# mapleCUx_large_400-003.net
KiCad netlist of a schematic drawn in EAGLE
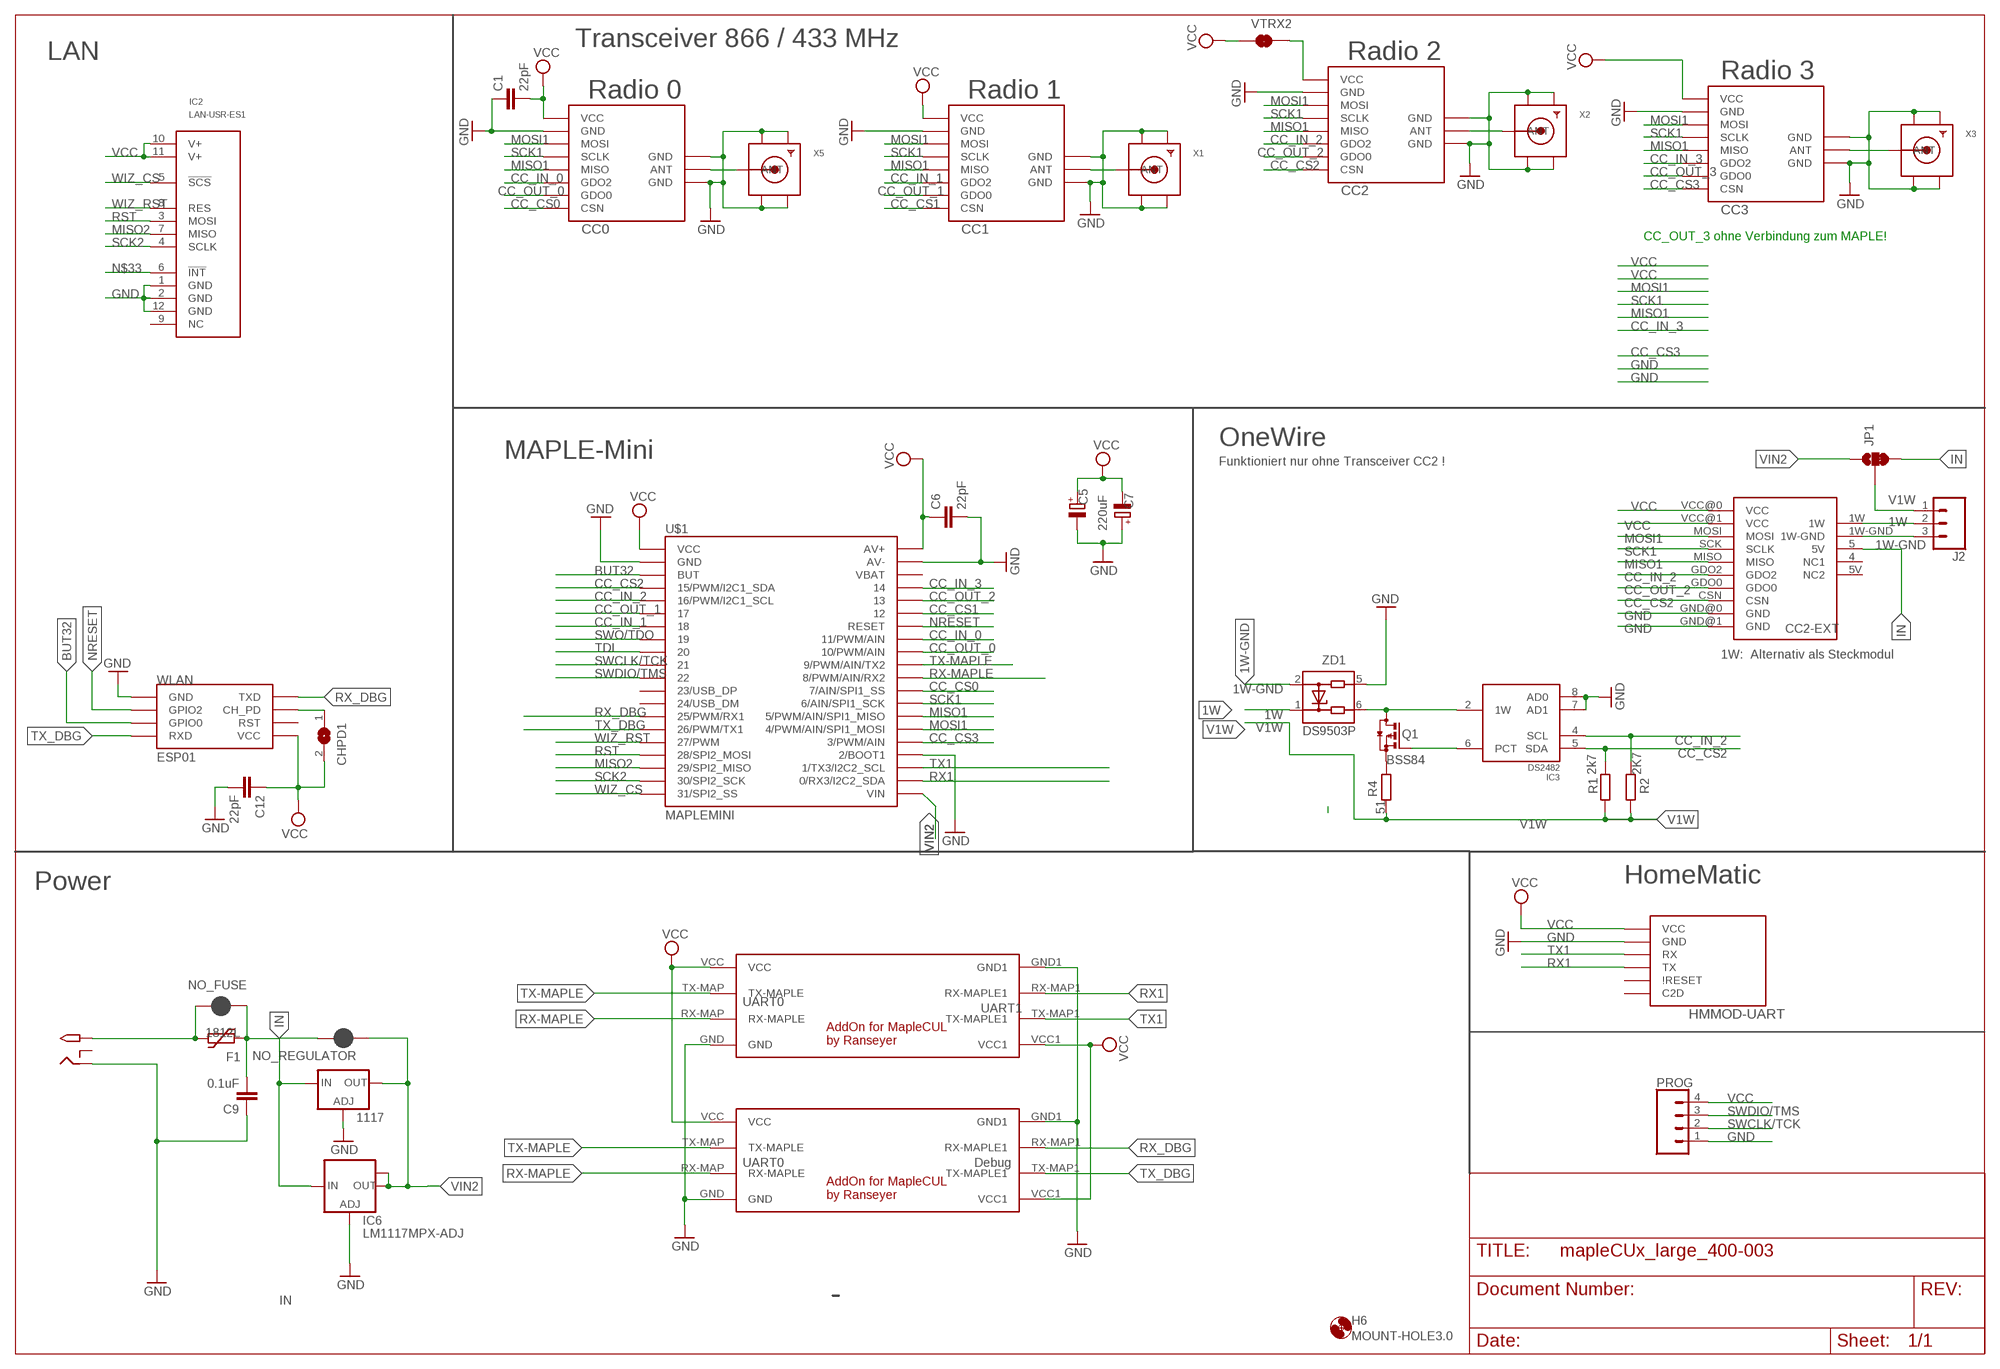
[diagram p0: schematic, sheet 1]

(export (version "E")
  (design (tool "Eeschema 10.0.6"))
  (components
    (comp (ref "1117")
      (value "LD117ADT50TR")
      (footprint "eagle-import:DPACK")
      (libsource (lib "eagle-import") (part "LD117A?DT50TR"))
    )
    (comp (ref "C1")
      (value "22pF")
      (footprint "eagle-import:C0805")
      (libsource (lib "eagle-import") (part "C-EUC0805"))
    )
    (comp (ref "C5")
      (value "220uF")
      (footprint "eagle-import:E5-8,5")
      (libsource (lib "eagle-import") (part "CPOL-EUE5-8.5"))
    )
    (comp (ref "C6")
      (value "22pF")
      (footprint "eagle-import:C0805")
      (libsource (lib "eagle-import") (part "C-EUC0805"))
    )
    (comp (ref "C7")
      (value "CPOL-EUSMCE")
      (footprint "eagle-import:SMC_E")
      (libsource (lib "eagle-import") (part "rcl_334_CPOL-EUSMCE"))
    )
    (comp (ref "C9")
      (value "0.1uF")
      (footprint "eagle-import:C1206")
      (libsource (lib "eagle-import") (part "C-EUC1206"))
    )
    (comp (ref "C12")
      (value "22pF")
      (footprint "eagle-import:C0805")
      (libsource (lib "eagle-import") (part "C-EUC0805"))
    )
    (comp (ref "CC0")
      (value "CC1101")
      (footprint "eagle-import:CC1101_MODULE1_SMD")
      (libsource (lib "eagle-import") (part "CC1101_MODULE1SMD"))
    )
    (comp (ref "CC1")
      (value "CC1101_MODULE1SMD")
      (footprint "eagle-import:CC1101_MODULE1_SMD")
      (libsource (lib "eagle-import") (part "CC1101_MODULE1SMD"))
    )
    (comp (ref "CC2")
      (value "CC1101_MODULE1SMD")
      (footprint "eagle-import:CC1101_MODULE1_SMD")
      (libsource (lib "eagle-import") (part "CC1101_MODULE1SMD"))
    )
    (comp (ref "CC2-EXT")
      (value "ONEWIRE-MODULE")
      (footprint "eagle-import:ONEWIRE_CC1101_MODULE3_DIL")
      (libsource (lib "eagle-import") (part "ONEWIRE-MODULE"))
    )
    (comp (ref "CC3")
      (value "CC1101_MODULE1SMD")
      (footprint "eagle-import:CC1101_MODULE1_SMD")
      (libsource (lib "eagle-import") (part "CC1101_MODULE1SMD"))
    )
    (comp (ref "CHPD1")
      (value "SJ")
      (footprint "eagle-import:SJ")
      (libsource (lib "eagle-import") (part "SJ"))
    )
    (comp (ref "F1")
      (value "1812L")
      (footprint "eagle-import:1812L")
      (libsource (lib "eagle-import") (part "1812L"))
    )
    (comp (ref "H6")
      (value "MOUNT-HOLE3.0")
      (footprint "eagle-import:3,0")
      (libsource (lib "eagle-import") (part "MOUNT-HOLE3.0"))
    )
    (comp (ref "HMMOD-UART")
      (value "HM-MOD-UARTDIL")
      (footprint "eagle-import:HM-MOD-UART-DIL")
      (libsource (lib "eagle-import") (part "HM-MOD-UARTDIL"))
    )
    (comp (ref "IC2")
      (value "LAN-USR-ES1")
      (footprint "eagle-import:USR-ES1")
      (libsource (lib "eagle-import") (part "LAN-USR-ES1"))
    )
    (comp (ref "IC3")
      (value "DS2482")
      (footprint "eagle-import:SO08")
      (libsource (lib "eagle-import") (part "DS2482-100S"))
    )
    (comp (ref "IC6")
      (value "LM1117MPX-ADJ")
      (footprint "eagle-import:SOT223")
      (libsource (lib "eagle-import") (part "LM1117MPX-ADJ"))
    )
    (comp (ref "J2")
      (value "CONN_03LONGPADS")
      (footprint "eagle-import:1X03_LONGPADS")
      (libsource (lib "eagle-import") (part "CONN_03LONGPADS"))
    )
    (comp (ref "JP1")
      (value "JUMPER-SMT_3_1-NC_TRACE_SILK")
      (footprint "eagle-import:SMT-JUMPER_3_1-NC_TRACE_SILK")
      (libsource (lib "eagle-import") (part "JUMPER-SMT_3_1-NC_TRACE_SILK"))
    )
    (comp (ref "NO_FUSE")
      (value "JUMPER-SMT_2_NC_PASTE_NO-SILK")
      (footprint "eagle-import:SMT-JUMPER_2_NC_PASTE_NO-SILK")
      (libsource (lib "eagle-import") (part "JUMPER-SMT_2_NC_PASTE_NO-SILK"))
    )
    (comp (ref "NO_REGULATOR")
      (value "JUMPER-SMT_2_NC_PASTE_NO-SILK")
      (footprint "eagle-import:SMT-JUMPER_2_NC_PASTE_NO-SILK")
      (libsource (lib "eagle-import") (part "JUMPER-SMT_2_NC_PASTE_NO-SILK"))
    )
    (comp (ref "PROG")
      (value "CONN_04LOCK")
      (footprint "eagle-import:1X04_LOCK")
      (libsource (lib "eagle-import") (part "CONN_04LOCK"))
    )
    (comp (ref "Q1")
      (value "BSS84")
      (footprint "eagle-import:SOT23")
      (libsource (lib "eagle-import") (part "BSS84"))
    )
    (comp (ref "R1")
      (value "2k7")
      (footprint "eagle-import:R0805")
      (libsource (lib "eagle-import") (part "R-EU_R0805"))
    )
    (comp (ref "R2")
      (value "2K7")
      (footprint "eagle-import:R0805")
      (libsource (lib "eagle-import") (part "R-EU_R0805"))
    )
    (comp (ref "R4")
      (value "51")
      (footprint "eagle-import:R0805")
      (libsource (lib "eagle-import") (part "R-EU_R0805"))
    )
    (comp (ref "U$1")
      (value "MAPLEMINI")
      (footprint "eagle-import:20-DIP")
      (libsource (lib "eagle-import") (part "MAPLEMINI"))
    )
    (comp (ref "U$2")
      (value "2.1MMJACKTHM")
      (footprint "eagle-import:PJ-102A")
      (libsource (lib "eagle-import") (part "2.1MMJACKTHM"))
    )
    (comp (ref "U$3")
      (value "MAPLE-CUL-ADDON-V01")
      (footprint "eagle-import:MAPLE-CUL-V01")
      (libsource (lib "eagle-import") (part "MAPLE-CUL-ADDON-V01"))
    )
    (comp (ref "U$4")
      (value "MAPLE-CUL-ADDON-V01")
      (footprint "eagle-import:MAPLE-CUL-V01")
      (libsource (lib "eagle-import") (part "MAPLE-CUL-ADDON-V01"))
    )
    (comp (ref "VTRX2")
      (value "JUMPER-SMT_2_NC_TRACE_SILK")
      (footprint "eagle-import:SMT-JUMPER_2_NC_TRACE_SILK")
      (libsource (lib "eagle-import") (part "JUMPER-SMT_2_NC_TRACE_SILK"))
    )
    (comp (ref "WLAN")
      (value "ESP01")
      (footprint "eagle-import:ESP01")
      (libsource (lib "eagle-import") (part "ESP01"))
    )
    (comp (ref "X1")
      (value "SMACONNECTOR_EDGE")
      (footprint "eagle-import:SMA_EDGELAUNCH")
      (libsource (lib "eagle-import") (part "SMACONNECTOR_EDGE"))
    )
    (comp (ref "X2")
      (value "SMACONNECTOR_EDGE")
      (footprint "eagle-import:SMA_EDGELAUNCH")
      (libsource (lib "eagle-import") (part "SMACONNECTOR_EDGE"))
    )
    (comp (ref "X3")
      (value "SMACONNECTOR_EDGE")
      (footprint "eagle-import:SMA_EDGELAUNCH")
      (libsource (lib "eagle-import") (part "SMACONNECTOR_EDGE"))
    )
    (comp (ref "X5")
      (value "SMACONNECTOR_EDGE")
      (footprint "eagle-import:SMA_EDGELAUNCH")
      (libsource (lib "eagle-import") (part "SMACONNECTOR_EDGE"))
    )
    (comp (ref "ZD1")
      (value "DS9503P")
      (footprint "eagle-import:TSOC6")
      (libsource (lib "eagle-import") (part "DS9503P"))
    )
  )
  (nets
    (net (code "1") (name "/CC_CS0") (class "Default")
      (node (ref "CC0") (pin "CSN") (pinfunction "CSN_CSN") (pintype "bidirectional"))
      (node (ref "U$1") (pin "29") (pinfunction "7/AIN/SPI1_SS_29") (pintype "bidirectional"))
    )
    (net (code "2") (name "/CC_CS1") (class "Default")
      (node (ref "CC1") (pin "CSN") (pinfunction "CSN_CSN") (pintype "bidirectional"))
      (node (ref "U$1") (pin "35") (pinfunction "12_35") (pintype "bidirectional"))
    )
    (net (code "3") (name "/CC_CS2") (class "Default")
      (node (ref "CC2") (pin "CSN") (pinfunction "CSN_CSN") (pintype "bidirectional"))
      (node (ref "CC2-EXT") (pin "CSN") (pinfunction "CSN_CSN") (pintype "bidirectional"))
      (node (ref "IC3") (pin "5") (pinfunction "SDA_5") (pintype "bidirectional"))
      (node (ref "R1") (pin "2") (pinfunction "2_2") (pintype "passive"))
      (node (ref "U$1") (pin "4") (pinfunction "15/PWM/I2C1_SDA_4") (pintype "bidirectional"))
    )
    (net (code "4") (name "/CC_CS3") (class "Default")
      (node (ref "CC3") (pin "CSN") (pinfunction "CSN_CSN") (pintype "bidirectional"))
      (node (ref "U$1") (pin "25") (pinfunction "3/PWM/AIN_25") (pintype "bidirectional"))
    )
    (net (code "5") (name "/CC_IN_0") (class "Default")
      (node (ref "CC0") (pin "GDO2") (pinfunction "GDO2_GDO2") (pintype "bidirectional"))
      (node (ref "U$1") (pin "33") (pinfunction "11/PWM/AIN_33") (pintype "bidirectional"))
    )
    (net (code "6") (name "/CC_IN_1") (class "Default")
      (node (ref "CC1") (pin "GDO2") (pinfunction "GDO2_GDO2") (pintype "bidirectional"))
      (node (ref "U$1") (pin "7") (pinfunction "18_7") (pintype "bidirectional"))
    )
    (net (code "7") (name "/CC_IN_2") (class "Default")
      (node (ref "CC2") (pin "GDO2") (pinfunction "GDO2_GDO2") (pintype "bidirectional"))
      (node (ref "CC2-EXT") (pin "GDO2") (pinfunction "GDO2_GDO2") (pintype "bidirectional"))
      (node (ref "IC3") (pin "4") (pinfunction "SCL_4") (pintype "input"))
      (node (ref "R2") (pin "2") (pinfunction "2_2") (pintype "passive"))
      (node (ref "U$1") (pin "5") (pinfunction "16/PWM/I2C1_SCL_5") (pintype "bidirectional"))
    )
    (net (code "8") (name "/CC_IN_3") (class "Default")
      (node (ref "CC3") (pin "GDO2") (pinfunction "GDO2_GDO2") (pintype "bidirectional"))
      (node (ref "U$1") (pin "37") (pinfunction "14_37") (pintype "bidirectional"))
    )
    (net (code "9") (name "/CC_OUT_0") (class "Default")
      (node (ref "CC0") (pin "GDO0") (pinfunction "GDO0_GDO0") (pintype "bidirectional"))
      (node (ref "U$1") (pin "32") (pinfunction "10/PWM/AIN_32") (pintype "bidirectional"))
    )
    (net (code "10") (name "/CC_OUT_1") (class "Default")
      (node (ref "CC1") (pin "GDO0") (pinfunction "GDO0_GDO0") (pintype "bidirectional"))
      (node (ref "U$1") (pin "6") (pinfunction "17_6") (pintype "bidirectional"))
    )
    (net (code "11") (name "/CC_OUT_2") (class "Default")
      (node (ref "CC2") (pin "GDO0") (pinfunction "GDO0_GDO0") (pintype "bidirectional"))
      (node (ref "CC2-EXT") (pin "GDO0") (pinfunction "GDO0_GDO0") (pintype "bidirectional"))
      (node (ref "U$1") (pin "36") (pinfunction "13_36") (pintype "bidirectional"))
    )
    (net (code "12") (name "/CC_OUT_3") (class "Default")
      (node (ref "CC3") (pin "GDO0") (pinfunction "GDO0_GDO0") (pintype "bidirectional"))
    )
    (net (code "13") (name "/MISO1") (class "Default")
      (node (ref "CC0") (pin "MISO") (pinfunction "MISO_MISO") (pintype "bidirectional"))
      (node (ref "CC1") (pin "MISO") (pinfunction "MISO_MISO") (pintype "bidirectional"))
      (node (ref "CC2") (pin "MISO") (pinfunction "MISO_MISO") (pintype "bidirectional"))
      (node (ref "CC2-EXT") (pin "MISO") (pinfunction "MISO_MISO") (pintype "bidirectional"))
      (node (ref "CC3") (pin "MISO") (pinfunction "MISO_MISO") (pintype "bidirectional"))
      (node (ref "U$1") (pin "27") (pinfunction "5/PWM/AIN/SPI1_MISO_27") (pintype "bidirectional"))
    )
    (net (code "14") (name "/MISO2") (class "Default")
      (node (ref "IC2") (pin "7") (pinfunction "MISO_7") (pintype "bidirectional"))
      (node (ref "U$1") (pin "18") (pinfunction "29/SPI2_MISO_18") (pintype "bidirectional"))
    )
    (net (code "15") (name "/MOSI1") (class "Default")
      (node (ref "CC0") (pin "MOSI") (pinfunction "MOSI_MOSI") (pintype "bidirectional"))
      (node (ref "CC1") (pin "MOSI") (pinfunction "MOSI_MOSI") (pintype "bidirectional"))
      (node (ref "CC2") (pin "MOSI") (pinfunction "MOSI_MOSI") (pintype "bidirectional"))
      (node (ref "CC2-EXT") (pin "MOSI") (pinfunction "MOSI_MOSI") (pintype "bidirectional"))
      (node (ref "CC3") (pin "MOSI") (pinfunction "MOSI_MOSI") (pintype "bidirectional"))
      (node (ref "U$1") (pin "26") (pinfunction "4/PWM/AIN/SPI1_MOSI_26") (pintype "bidirectional"))
    )
    (net (code "16") (name "/N$33") (class "Default")
      (node (ref "IC2") (pin "6") (pinfunction "~{INT}_6") (pintype "output"))
    )
    (net (code "17") (name "/RST") (class "Default")
      (node (ref "IC2") (pin "3") (pinfunction "MOSI_3") (pintype "bidirectional"))
      (node (ref "U$1") (pin "17") (pinfunction "28/SPI2_MOSI_17") (pintype "bidirectional"))
    )
    (net (code "18") (name "/SCK1") (class "Default")
      (node (ref "CC0") (pin "SCLK") (pinfunction "SCLK_SCLK") (pintype "bidirectional"))
      (node (ref "CC1") (pin "SCLK") (pinfunction "SCLK_SCLK") (pintype "bidirectional"))
      (node (ref "CC2") (pin "SCLK") (pinfunction "SCLK_SCLK") (pintype "bidirectional"))
      (node (ref "CC2-EXT") (pin "SCK") (pinfunction "SCLK_SCK") (pintype "bidirectional"))
      (node (ref "CC3") (pin "SCLK") (pinfunction "SCLK_SCLK") (pintype "bidirectional"))
      (node (ref "U$1") (pin "28") (pinfunction "6/AIN/SPI1_SCK_28") (pintype "bidirectional"))
    )
    (net (code "19") (name "/SCK2") (class "Default")
      (node (ref "IC2") (pin "4") (pinfunction "SCLK_4") (pintype "input"))
      (node (ref "U$1") (pin "19") (pinfunction "30/SPI2_SCK_19") (pintype "bidirectional"))
    )
    (net (code "20") (name "/SWCLK{slash}TCK") (class "Default")
      (node (ref "PROG") (pin "2") (pinfunction "2_2") (pintype "passive"))
      (node (ref "U$1") (pin "10") (pinfunction "21_10") (pintype "bidirectional"))
    )
    (net (code "21") (name "/SWDIO{slash}TMS") (class "Default")
      (node (ref "PROG") (pin "3") (pinfunction "3_3") (pintype "passive"))
      (node (ref "U$1") (pin "11") (pinfunction "22_11") (pintype "bidirectional"))
    )
    (net (code "22") (name "/SWO{slash}TDO") (class "Default")
      (node (ref "U$1") (pin "8") (pinfunction "19_8") (pintype "bidirectional"))
    )
    (net (code "23") (name "/TDI") (class "Default")
      (node (ref "U$1") (pin "9") (pinfunction "20_9") (pintype "bidirectional"))
    )
    (net (code "24") (name "/WIZ_CS") (class "Default")
      (node (ref "IC2") (pin "5") (pinfunction "~{SCS}_5") (pintype "input"))
      (node (ref "U$1") (pin "20") (pinfunction "31/SPI2_SS_20") (pintype "bidirectional"))
    )
    (net (code "25") (name "/WIZ_RST") (class "Default")
      (node (ref "IC2") (pin "8") (pinfunction "RES_8") (pintype "input"))
      (node (ref "U$1") (pin "16") (pinfunction "27/PWM_16") (pintype "bidirectional"))
    )
    (net (code "26") (name "1W") (class "Default")
      (node (ref "CC2-EXT") (pin "1W") (pinfunction "1W_1W") (pintype "bidirectional"))
      (node (ref "J2") (pin "2") (pinfunction "2_2") (pintype "passive"))
      (node (ref "ZD1") (pin "1") (pinfunction "P$1_1") (pintype "passive"))
    )
    (net (code "27") (name "1W-GND") (class "Default")
      (node (ref "CC2-EXT") (pin "1W-GND") (pinfunction "1W-GND_1W-GND") (pintype "bidirectional"))
      (node (ref "J2") (pin "3") (pinfunction "3_3") (pintype "passive"))
      (node (ref "ZD1") (pin "2") (pinfunction "P$2_2") (pintype "passive"))
    )
    (net (code "28") (name "BUT32") (class "Default")
      (node (ref "U$1") (pin "3") (pinfunction "BUT_3") (pintype "bidirectional"))
      (node (ref "WLAN") (pin "GPIO0") (pinfunction "GPIO0_GPIO0") (pintype "bidirectional"))
    )
    (net (code "29") (name "GND") (class "Default")
      (node (ref "1117") (pin "1") (pinfunction "ADJ_1") (pintype "input"))
      (node (ref "C1") (pin "1") (pinfunction "1_1") (pintype "passive"))
      (node (ref "C12") (pin "2") (pinfunction "2_2") (pintype "passive"))
      (node (ref "C5") (pin "-") (pinfunction "-_-") (pintype "passive"))
      (node (ref "C6") (pin "2") (pinfunction "2_2") (pintype "passive"))
      (node (ref "C7") (pin "+") (pinfunction "+_+") (pintype "passive"))
      (node (ref "C9") (pin "1") (pinfunction "1_1") (pintype "passive"))
      (node (ref "CC0") (pin "GND@0") (pinfunction "GND_GND@0") (pintype "power_in"))
      (node (ref "CC0") (pin "GND@1") (pinfunction "GND_GND@1") (pintype "power_in"))
      (node (ref "CC0") (pin "GND@2") (pinfunction "GND_GND@2") (pintype "power_in"))
      (node (ref "CC1") (pin "GND@0") (pinfunction "GND_GND@0") (pintype "power_in"))
      (node (ref "CC1") (pin "GND@1") (pinfunction "GND_GND@1") (pintype "power_in"))
      (node (ref "CC1") (pin "GND@2") (pinfunction "GND_GND@2") (pintype "power_in"))
      (node (ref "CC2") (pin "GND@0") (pinfunction "GND_GND@0") (pintype "power_in"))
      (node (ref "CC2") (pin "GND@1") (pinfunction "GND_GND@1") (pintype "power_in"))
      (node (ref "CC2") (pin "GND@2") (pinfunction "GND_GND@2") (pintype "power_in"))
      (node (ref "CC2-EXT") (pin "GND@0") (pinfunction "GND_GND@0") (pintype "power_in"))
      (node (ref "CC2-EXT") (pin "GND@1") (pinfunction "GND_GND@1") (pintype "power_in"))
      (node (ref "CC3") (pin "GND@0") (pinfunction "GND_GND@0") (pintype "power_in"))
      (node (ref "CC3") (pin "GND@1") (pinfunction "GND_GND@1") (pintype "power_in"))
      (node (ref "CC3") (pin "GND@2") (pinfunction "GND_GND@2") (pintype "power_in"))
      (node (ref "HMMOD-UART") (pin "2") (pinfunction "GND_2") (pintype "power_in"))
      (node (ref "IC2") (pin "1") (pinfunction "GND_1") (pintype "power_in"))
      (node (ref "IC2") (pin "12") (pinfunction "GND_12") (pintype "power_in"))
      (node (ref "IC2") (pin "2") (pinfunction "GND_2") (pintype "power_in"))
      (node (ref "IC3") (pin "7") (pinfunction "AD1_7") (pintype "input"))
      (node (ref "IC3") (pin "8") (pinfunction "AD0_8") (pintype "input"))
      (node (ref "IC6") (pin "1") (pinfunction "ADJ_1") (pintype "input"))
      (node (ref "PROG") (pin "1") (pinfunction "1_1") (pintype "passive"))
      (node (ref "U$1") (pin "2") (pinfunction "GND_2") (pintype "bidirectional"))
      (node (ref "U$1") (pin "24") (pinfunction "2/BOOT1_24") (pintype "bidirectional"))
      (node (ref "U$1") (pin "39") (pinfunction "AV-_39") (pintype "bidirectional"))
      (node (ref "U$2") (pin "RING") (pinfunction "RING_RING") (pintype "bidirectional"))
      (node (ref "U$3") (pin "GND") (pinfunction "GND_GND") (pintype "bidirectional"))
      (node (ref "U$3") (pin "GND1") (pinfunction "GND1_GND1") (pintype "bidirectional"))
      (node (ref "U$4") (pin "GND") (pinfunction "GND_GND") (pintype "bidirectional"))
      (node (ref "U$4") (pin "GND1") (pinfunction "GND1_GND1") (pintype "bidirectional"))
      (node (ref "WLAN") (pin "GND") (pinfunction "GND_GND") (pintype "bidirectional"))
      (node (ref "X1") (pin "GND@1") (pinfunction "GND4_GND@1") (pintype "power_in"))
      (node (ref "X1") (pin "GND@2") (pinfunction "GND3_GND@2") (pintype "power_in"))
      (node (ref "X1") (pin "GND@3") (pinfunction "GND2_GND@3") (pintype "power_in"))
      (node (ref "X1") (pin "GND@4") (pinfunction "GND1_GND@4") (pintype "power_in"))
      (node (ref "X2") (pin "GND@1") (pinfunction "GND4_GND@1") (pintype "power_in"))
      (node (ref "X2") (pin "GND@2") (pinfunction "GND3_GND@2") (pintype "power_in"))
      (node (ref "X2") (pin "GND@3") (pinfunction "GND2_GND@3") (pintype "power_in"))
      (node (ref "X2") (pin "GND@4") (pinfunction "GND1_GND@4") (pintype "power_in"))
      (node (ref "X3") (pin "GND@1") (pinfunction "GND4_GND@1") (pintype "power_in"))
      (node (ref "X3") (pin "GND@2") (pinfunction "GND3_GND@2") (pintype "power_in"))
      (node (ref "X3") (pin "GND@3") (pinfunction "GND2_GND@3") (pintype "power_in"))
      (node (ref "X3") (pin "GND@4") (pinfunction "GND1_GND@4") (pintype "power_in"))
      (node (ref "X5") (pin "GND@1") (pinfunction "GND4_GND@1") (pintype "power_in"))
      (node (ref "X5") (pin "GND@2") (pinfunction "GND3_GND@2") (pintype "power_in"))
      (node (ref "X5") (pin "GND@3") (pinfunction "GND2_GND@3") (pintype "power_in"))
      (node (ref "X5") (pin "GND@4") (pinfunction "GND1_GND@4") (pintype "power_in"))
      (node (ref "ZD1") (pin "5") (pinfunction "P$3_5") (pintype "passive"))
    )
    (net (code "30") (name "IN") (class "Default")
      (node (ref "1117") (pin "3") (pinfunction "IN_3") (pintype "input"))
      (node (ref "C9") (pin "2") (pinfunction "2_2") (pintype "passive"))
      (node (ref "CC2-EXT") (pin "5") (pinfunction "5V_5") (pintype "bidirectional"))
      (node (ref "F1") (pin "P$1") (pinfunction "1_P$1") (pintype "passive"))
      (node (ref "IC6") (pin "3") (pinfunction "IN_3") (pintype "input"))
      (node (ref "JP1") (pin "3") (pinfunction "3_3") (pintype "passive"))
      (node (ref "NO_FUSE") (pin "1") (pinfunction "1_1") (pintype "passive"))
      (node (ref "NO_REGULATOR") (pin "2") (pinfunction "2_2") (pintype "passive"))
    )
    (net (code "31") (name "NRESET") (class "Default")
      (node (ref "U$1") (pin "34") (pinfunction "RESET_34") (pintype "bidirectional"))
      (node (ref "WLAN") (pin "GPIO2") (pinfunction "GPIO2_GPIO2") (pintype "bidirectional"))
    )
    (net (code "32") (name "Net-(CC2-PadVCC)") (class "Default")
      (node (ref "CC2") (pin "VCC") (pinfunction "VCC_VCC") (pintype "power_in"))
      (node (ref "VTRX2") (pin "2") (pinfunction "2_2") (pintype "passive"))
    )
    (net (code "33") (name "Net-(CHPD1-Pad1)") (class "Default")
      (node (ref "CHPD1") (pin "1") (pinfunction "1_1") (pintype "passive"))
      (node (ref "WLAN") (pin "CH_PD") (pinfunction "CH_PD_CH_PD") (pintype "bidirectional"))
    )
    (net (code "34") (name "Net-(F1-2)") (class "Default")
      (node (ref "F1") (pin "P$2") (pinfunction "2_P$2") (pintype "passive"))
      (node (ref "NO_FUSE") (pin "2") (pinfunction "2_2") (pintype "passive"))
      (node (ref "U$2") (pin "TIP") (pinfunction "TIP_TIP") (pintype "bidirectional"))
    )
    (net (code "35") (name "Net-(IC3A-1W)") (class "Default")
      (node (ref "IC3") (pin "2") (pinfunction "1W_2") (pintype "open_collector"))
      (node (ref "Q1") (pin "3") (pinfunction "D_3") (pintype "passive"))
      (node (ref "ZD1") (pin "6") (pinfunction "P$4_6") (pintype "passive"))
    )
    (net (code "36") (name "Net-(IC3A-PCT)") (class "Default")
      (node (ref "IC3") (pin "6") (pinfunction "PCT_6") (pintype "output"))
      (node (ref "Q1") (pin "1") (pinfunction "G_1") (pintype "passive"))
    )
    (net (code "37") (name "Net-(Q1-S)") (class "Default")
      (node (ref "Q1") (pin "2") (pinfunction "S_2") (pintype "passive"))
      (node (ref "R4") (pin "1") (pinfunction "1_1") (pintype "passive"))
    )
    (net (code "38") (name "Net-(X1-ANT)") (class "Default")
      (node (ref "CC1") (pin "ANT") (pinfunction "ANT_ANT") (pintype "output"))
      (node (ref "X1") (pin "P") (pinfunction "ANT_P") (pintype "bidirectional"))
    )
    (net (code "39") (name "Net-(X2-ANT)") (class "Default")
      (node (ref "CC2") (pin "ANT") (pinfunction "ANT_ANT") (pintype "output"))
      (node (ref "X2") (pin "P") (pinfunction "ANT_P") (pintype "bidirectional"))
    )
    (net (code "40") (name "Net-(X3-ANT)") (class "Default")
      (node (ref "CC3") (pin "ANT") (pinfunction "ANT_ANT") (pintype "output"))
      (node (ref "X3") (pin "P") (pinfunction "ANT_P") (pintype "bidirectional"))
    )
    (net (code "41") (name "Net-(X5-ANT)") (class "Default")
      (node (ref "CC0") (pin "ANT") (pinfunction "ANT_ANT") (pintype "output"))
      (node (ref "X5") (pin "P") (pinfunction "ANT_P") (pintype "bidirectional"))
    )
    (net (code "42") (name "RX-MAPLE") (class "Default")
      (node (ref "U$1") (pin "30") (pinfunction "8/PWM/AIN/RX2_30") (pintype "bidirectional"))
      (node (ref "U$3") (pin "RX-MAP") (pinfunction "RX-MAPLE_RX-MAP") (pintype "bidirectional"))
      (node (ref "U$4") (pin "RX-MAP") (pinfunction "RX-MAPLE_RX-MAP") (pintype "bidirectional"))
    )
    (net (code "43") (name "RX1") (class "Default")
      (node (ref "HMMOD-UART") (pin "5") (pinfunction "TX_5") (pintype "bidirectional"))
      (node (ref "U$1") (pin "22") (pinfunction "0/RX3/I2C2_SDA_22") (pintype "bidirectional"))
      (node (ref "U$3") (pin "RX-MAP1") (pinfunction "RX-MAPLE1_RX-MAP1") (pintype "bidirectional"))
    )
    (net (code "44") (name "RX_DBG") (class "Default")
      (node (ref "U$1") (pin "14") (pinfunction "25/PWM/RX1_14") (pintype "bidirectional"))
      (node (ref "U$4") (pin "RX-MAP1") (pinfunction "RX-MAPLE1_RX-MAP1") (pintype "bidirectional"))
      (node (ref "WLAN") (pin "TX") (pinfunction "TXD_TX") (pintype "bidirectional"))
    )
    (net (code "45") (name "TX-MAPLE") (class "Default")
      (node (ref "U$1") (pin "31") (pinfunction "9/PWM/AIN/TX2_31") (pintype "bidirectional"))
      (node (ref "U$3") (pin "TX-MAP") (pinfunction "TX-MAPLE_TX-MAP") (pintype "bidirectional"))
      (node (ref "U$4") (pin "TX-MAP") (pinfunction "TX-MAPLE_TX-MAP") (pintype "bidirectional"))
    )
    (net (code "46") (name "TX1") (class "Default")
      (node (ref "HMMOD-UART") (pin "6") (pinfunction "RX_6") (pintype "bidirectional"))
      (node (ref "U$1") (pin "23") (pinfunction "1/TX3/I2C2_SCL_23") (pintype "bidirectional"))
      (node (ref "U$3") (pin "TX-MAP1") (pinfunction "TX-MAPLE1_TX-MAP1") (pintype "bidirectional"))
    )
    (net (code "47") (name "TX_DBG") (class "Default")
      (node (ref "U$1") (pin "15") (pinfunction "26/PWM/TX1_15") (pintype "bidirectional"))
      (node (ref "U$4") (pin "TX-MAP1") (pinfunction "TX-MAPLE1_TX-MAP1") (pintype "bidirectional"))
      (node (ref "WLAN") (pin "RX") (pinfunction "RXD_RX") (pintype "bidirectional"))
    )
    (net (code "48") (name "V1W") (class "Default")
      (node (ref "J2") (pin "1") (pinfunction "1_1") (pintype "passive"))
      (node (ref "JP1") (pin "2") (pinfunction "2_2") (pintype "passive"))
      (node (ref "R1") (pin "1") (pinfunction "1_1") (pintype "passive"))
      (node (ref "R2") (pin "1") (pinfunction "1_1") (pintype "passive"))
      (node (ref "R4") (pin "2") (pinfunction "2_2") (pintype "passive"))
    )
    (net (code "49") (name "VCC") (class "Default")
      (node (ref "C1") (pin "2") (pinfunction "2_2") (pintype "passive"))
      (node (ref "C12") (pin "1") (pinfunction "1_1") (pintype "passive"))
      (node (ref "C5") (pin "+") (pinfunction "+_+") (pintype "passive"))
      (node (ref "C6") (pin "1") (pinfunction "1_1") (pintype "passive"))
      (node (ref "C7") (pin "-") (pinfunction "-_-") (pintype "passive"))
      (node (ref "CC0") (pin "VCC") (pinfunction "VCC_VCC") (pintype "power_in"))
      (node (ref "CC1") (pin "VCC") (pinfunction "VCC_VCC") (pintype "power_in"))
      (node (ref "CC2-EXT") (pin "VCC@0") (pinfunction "VCC_VCC@0") (pintype "power_in"))
      (node (ref "CC2-EXT") (pin "VCC@1") (pinfunction "VCC_VCC@1") (pintype "power_in"))
      (node (ref "CC3") (pin "VCC") (pinfunction "VCC_VCC") (pintype "power_in"))
      (node (ref "CHPD1") (pin "2") (pinfunction "2_2") (pintype "passive"))
      (node (ref "HMMOD-UART") (pin "1") (pinfunction "VCC_1") (pintype "power_in"))
      (node (ref "IC2") (pin "10") (pinfunction "V+_10") (pintype "power_in"))
      (node (ref "IC2") (pin "11") (pinfunction "V+_11") (pintype "power_in"))
      (node (ref "PROG") (pin "4") (pinfunction "4_4") (pintype "passive"))
      (node (ref "U$1") (pin "1") (pinfunction "VCC_1") (pintype "bidirectional"))
      (node (ref "U$1") (pin "40") (pinfunction "AV+_40") (pintype "bidirectional"))
      (node (ref "U$3") (pin "VCC") (pinfunction "VCC_VCC") (pintype "bidirectional"))
      (node (ref "U$3") (pin "VCC1") (pinfunction "VCC1_VCC1") (pintype "bidirectional"))
      (node (ref "U$4") (pin "VCC") (pinfunction "VCC_VCC") (pintype "bidirectional"))
      (node (ref "U$4") (pin "VCC1") (pinfunction "VCC1_VCC1") (pintype "bidirectional"))
      (node (ref "VTRX2") (pin "1") (pinfunction "1_1") (pintype "passive"))
      (node (ref "WLAN") (pin "VCC") (pinfunction "VCC_VCC") (pintype "bidirectional"))
    )
    (net (code "50") (name "VIN2") (class "Default")
      (node (ref "1117") (pin "4") (pinfunction "OUT_4") (pintype "passive"))
      (node (ref "IC6") (pin "2") (pinfunction "OUT_2") (pintype "passive"))
      (node (ref "IC6") (pin "TAB") (pinfunction "OUT1_TAB") (pintype "passive"))
      (node (ref "JP1") (pin "1") (pinfunction "1_1") (pintype "passive"))
      (node (ref "NO_REGULATOR") (pin "1") (pinfunction "1_1") (pintype "passive"))
      (node (ref "U$1") (pin "21") (pinfunction "VIN_21") (pintype "bidirectional"))
    )
    (net (code "51") (name "unconnected-(CC2-EXT-NC1-Pad4)") (class "Default")
      (node (ref "CC2-EXT") (pin "4") (pinfunction "NC1_4") (pintype "bidirectional"))
    )
    (net (code "52") (name "unconnected-(CC2-EXT-NC2-Pad5V)") (class "Default")
      (node (ref "CC2-EXT") (pin "5V") (pinfunction "NC2_5V") (pintype "bidirectional"))
    )
    (net (code "53") (name "unconnected-(HMMOD-UART-C2D-Pad3)") (class "Default")
      (node (ref "HMMOD-UART") (pin "3") (pinfunction "C2D_3") (pintype "bidirectional"))
    )
    (net (code "54") (name "unconnected-(HMMOD-UART-\\~{RESET}-Pad4)") (class "Default")
      (node (ref "HMMOD-UART") (pin "4") (pinfunction "\\~{RESET}_4") (pintype "bidirectional"))
    )
    (net (code "55") (name "unconnected-(IC2-NC-Pad9)") (class "Default")
      (node (ref "IC2") (pin "9") (pinfunction "NC_9") (pintype "no_connect"))
    )
    (net (code "56") (name "unconnected-(U$1-23{slash}USB_DP-Pad12)") (class "Default")
      (node (ref "U$1") (pin "12") (pinfunction "23/USB_DP_12") (pintype "bidirectional"))
    )
    (net (code "57") (name "unconnected-(U$1-24{slash}USB_DM-Pad13)") (class "Default")
      (node (ref "U$1") (pin "13") (pinfunction "24/USB_DM_13") (pintype "bidirectional"))
    )
    (net (code "58") (name "unconnected-(U$1-VBAT-Pad38)") (class "Default")
      (node (ref "U$1") (pin "38") (pinfunction "VBAT_38") (pintype "bidirectional"))
    )
    (net (code "59") (name "unconnected-(U$2-PadRING_SW)") (class "Default")
      (node (ref "U$2") (pin "RING_SW") (pinfunction "RING_SW_RING_SW") (pintype "bidirectional"))
    )
    (net (code "60") (name "unconnected-(WLAN-PadRST)") (class "Default")
      (node (ref "WLAN") (pin "RST") (pinfunction "RST_RST") (pintype "bidirectional"))
    )
  )
)
